# touch.net
KiCad netlist of a schematic drawn in Altium Designer
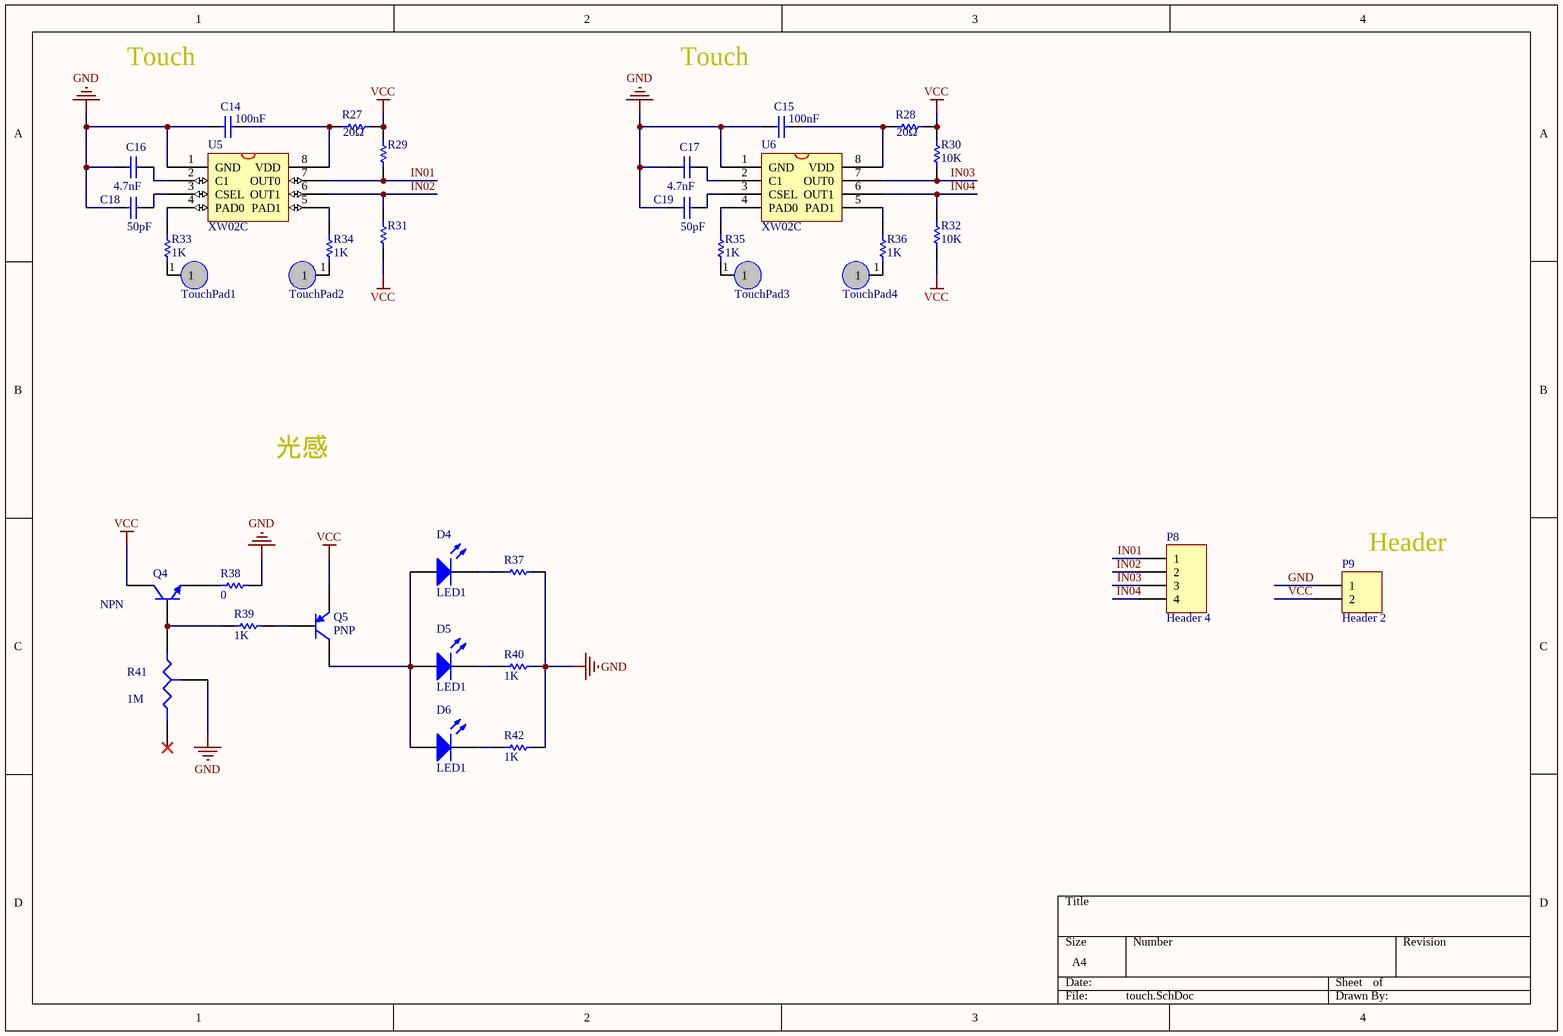
[diagram p0: touch.SchDoc]

(export (version "E")
  (design (tool "Eeschema 10.0.6"))
  (components
    (comp (ref "C14")
      (value "100nF")
      (footprint "0603p")
      (description "Capacitor")
      (fields (field (name "PUBLISHER") "Altium Limited"))
      (libsource (lib "Miscellaneous Devices") (part "Cap"))
    )
    (comp (ref "C15")
      (value "100nF")
      (footprint "0603p")
      (description "Capacitor")
      (fields (field (name "PUBLISHER") "Altium Limited"))
      (libsource (lib "Miscellaneous Devices") (part "Cap"))
    )
    (comp (ref "C16")
      (value "4.7nF")
      (footprint "0603p")
      (description "Capacitor")
      (fields (field (name "Comment") "4.7nf") (field (name "PUBLISHER") "Altium Limited"))
      (libsource (lib "Miscellaneous Devices") (part "Cap"))
    )
    (comp (ref "C17")
      (value "4.7nF")
      (footprint "0603p")
      (description "Capacitor")
      (fields (field (name "Comment") "4.7nf") (field (name "PUBLISHER") "Altium Limited"))
      (libsource (lib "Miscellaneous Devices") (part "Cap"))
    )
    (comp (ref "C18")
      (value "50pF")
      (footprint "0603p")
      (description "Capacitor")
      (fields (field (name "Comment") "50pf") (field (name "PUBLISHER") "Altium Limited"))
      (libsource (lib "Miscellaneous Devices") (part "Cap"))
    )
    (comp (ref "C19")
      (value "50pF")
      (footprint "0603p")
      (description "Capacitor")
      (fields (field (name "Comment") "50pf") (field (name "PUBLISHER") "Altium Limited"))
      (libsource (lib "Miscellaneous Devices") (part "Cap"))
    )
    (comp (ref "D4")
      (value "LED1")
      (footprint "0805")
      (description "Typical RED GaAs LED")
      (fields (field (name "PUBLISHER") "Altium Limited"))
      (libsource (lib "Miscellaneous Devices") (part "LED1"))
    )
    (comp (ref "D5")
      (value "LED1")
      (footprint "0805")
      (description "Typical RED GaAs LED")
      (fields (field (name "PUBLISHER") "Altium Limited"))
      (libsource (lib "Miscellaneous Devices") (part "LED1"))
    )
    (comp (ref "D6")
      (value "LED1")
      (footprint "0805")
      (description "Typical RED GaAs LED")
      (fields (field (name "PUBLISHER") "Altium Limited"))
      (libsource (lib "Miscellaneous Devices") (part "LED1"))
    )
    (comp (ref "P8")
      (value "Header 4")
      (footprint "HDR1X4")
      (description "Header, 4-Pin")
      (fields (field (name "PUBLISHER") "Altium Limited"))
      (libsource (lib "Miscellaneous Connectors") (part "Header 4"))
    )
    (comp (ref "P9")
      (value "Header 2")
      (footprint "HDR1X2")
      (description "Header, 2-Pin")
      (fields (field (name "PUBLISHER") "Altium Limited"))
      (libsource (lib "Miscellaneous Connectors") (part "Header 2"))
    )
    (comp (ref "Q4")
      (value "NPN")
      (footprint "TEMT6000X01")
      (description "NPN Bipolar Transistor")
      (fields (field (name "PUBLISHER") "Altium Limited"))
      (libsource (lib "Miscellaneous Devices") (part "NPN"))
    )
    (comp (ref "Q5")
      (value "PNP")
      (footprint "SOT-23R")
      (description "8550")
      (fields (field (name "PUBLISHER") "Altium Limited"))
      (libsource (lib "Miscellaneous Devices") (part "PNP"))
    )
    (comp (ref "R27")
      (value "20Ω")
      (footprint "0603p")
      (description "Resistor")
      (fields (field (name "PUBLISHER") "Altium Limited"))
      (libsource (lib "Miscellaneous Devices") (part "Res1"))
    )
    (comp (ref "R28")
      (value "20Ω")
      (footprint "0603p")
      (description "Resistor")
      (fields (field (name "PUBLISHER") "Altium Limited"))
      (libsource (lib "Miscellaneous Devices") (part "Res1"))
    )
    (comp (ref "R29")
      (value "10K")
      (footprint "0603p")
      (description "Resistor")
      (fields (field (name "PUBLISHER") "Altium Limited"))
      (libsource (lib "Miscellaneous Devices") (part "Res1"))
    )
    (comp (ref "R30")
      (value "10K")
      (footprint "0603p")
      (description "Resistor")
      (fields (field (name "PUBLISHER") "Altium Limited"))
      (libsource (lib "Miscellaneous Devices") (part "Res1"))
    )
    (comp (ref "R31")
      (value "10K")
      (footprint "0603p")
      (description "Resistor")
      (fields (field (name "PUBLISHER") "Altium Limited"))
      (libsource (lib "Miscellaneous Devices") (part "Res1"))
    )
    (comp (ref "R32")
      (value "10K")
      (footprint "0603p")
      (description "Resistor")
      (fields (field (name "PUBLISHER") "Altium Limited"))
      (libsource (lib "Miscellaneous Devices") (part "Res1"))
    )
    (comp (ref "R33")
      (value "1K")
      (footprint "0603p")
      (description "Resistor")
      (fields (field (name "PUBLISHER") "Altium Limited"))
      (libsource (lib "Miscellaneous Devices") (part "Res1"))
    )
    (comp (ref "R34")
      (value "1K")
      (footprint "0603p")
      (description "Resistor")
      (fields (field (name "PUBLISHER") "Altium Limited"))
      (libsource (lib "Miscellaneous Devices") (part "Res1"))
    )
    (comp (ref "R35")
      (value "1K")
      (footprint "0603p")
      (description "Resistor")
      (fields (field (name "PUBLISHER") "Altium Limited"))
      (libsource (lib "Miscellaneous Devices") (part "Res1"))
    )
    (comp (ref "R36")
      (value "1K")
      (footprint "0603p")
      (description "Resistor")
      (fields (field (name "PUBLISHER") "Altium Limited"))
      (libsource (lib "Miscellaneous Devices") (part "Res1"))
    )
    (comp (ref "R37")
      (value "1K")
      (footprint "0603p")
      (description "Resistor")
      (fields (field (name "PUBLISHER") "Altium Limited"))
      (libsource (lib "Miscellaneous Devices") (part "Res1"))
    )
    (comp (ref "R38")
      (value "0")
      (footprint "0603p")
      (description "Resistor")
      (fields (field (name "PUBLISHER") "Altium Limited"))
      (libsource (lib "Miscellaneous Devices") (part "Res1"))
    )
    (comp (ref "R39")
      (value "1K")
      (footprint "0603p")
      (description "Resistor")
      (libsource (lib "Miscellaneous Devices") (part "Res1"))
    )
    (comp (ref "R40")
      (value "1K")
      (footprint "0603p")
      (description "Resistor")
      (fields (field (name "PUBLISHER") "Altium Limited"))
      (libsource (lib "Miscellaneous Devices") (part "Res1"))
    )
    (comp (ref "R41")
      (value "1M")
      (footprint "RM063")
      (description "Tapped Resistor")
      (libsource (lib "Miscellaneous Devices") (part "Res Tap"))
    )
    (comp (ref "R42")
      (value "1K")
      (footprint "0603p")
      (description "Resistor")
      (fields (field (name "PUBLISHER") "Altium Limited"))
      (libsource (lib "Miscellaneous Devices") (part "Res1"))
    )
    (comp (ref "TouchPad1")
      (value "TouchPad")
      (footprint "TOUCHKEY - latch")
      (libsource (lib "PCB_Project1") (part "TouchPad"))
    )
    (comp (ref "TouchPad2")
      (value "TouchPad")
      (footprint "TOUCHKEY - latch")
      (libsource (lib "PCB_Project1") (part "TouchPad"))
    )
    (comp (ref "TouchPad3")
      (value "TouchPad")
      (footprint "TOUCHKEY - latch")
      (libsource (lib "PCB_Project1") (part "TouchPad"))
    )
    (comp (ref "TouchPad4")
      (value "TouchPad")
      (footprint "TOUCHKEY - latch")
      (libsource (lib "PCB_Project1") (part "TouchPad"))
    )
    (comp (ref "U5") (value "XW02C") (footprint "SOP-8L") (libsource (lib "EliteSTM32封装库") (part "24C256")))
    (comp (ref "U6") (value "XW02C") (footprint "SOP-8L") (libsource (lib "EliteSTM32封装库") (part "24C256")))
  )
  (nets
    (net (code "2") (name "/IN01") (class "Default")
      (node (ref "P8") (pin "1") (pinfunction "1_1") (pintype "passive"))
      (node (ref "R29") (pin "1") (pinfunction "1_1") (pintype "passive"))
      (node (ref "U5") (pin "7") (pinfunction "OUT0_7") (pintype "bidirectional"))
    )
    (net (code "3") (name "/IN02") (class "Default")
      (node (ref "P8") (pin "2") (pinfunction "2_2") (pintype "passive"))
      (node (ref "R31") (pin "2") (pinfunction "2_2") (pintype "passive"))
      (node (ref "U5") (pin "6") (pinfunction "OUT1_6") (pintype "bidirectional"))
    )
    (net (code "4") (name "/IN03") (class "Default")
      (node (ref "P8") (pin "3") (pinfunction "3_3") (pintype "passive"))
      (node (ref "R30") (pin "1") (pinfunction "1_1") (pintype "passive"))
      (node (ref "U6") (pin "7") (pinfunction "OUT0_7") (pintype "bidirectional"))
    )
    (net (code "5") (name "/IN04") (class "Default")
      (node (ref "P8") (pin "4") (pinfunction "4_4") (pintype "passive"))
      (node (ref "R32") (pin "2") (pinfunction "2_2") (pintype "passive"))
      (node (ref "U6") (pin "6") (pinfunction "OUT1_6") (pintype "bidirectional"))
    )
    (net (code "6") (name "GND") (class "Default")
      (node (ref "C14") (pin "1") (pinfunction "1_1") (pintype "passive"))
      (node (ref "C15") (pin "1") (pinfunction "1_1") (pintype "passive"))
      (node (ref "C16") (pin "1") (pinfunction "1_1") (pintype "passive"))
      (node (ref "C17") (pin "1") (pinfunction "1_1") (pintype "passive"))
      (node (ref "C18") (pin "1") (pinfunction "1_1") (pintype "passive"))
      (node (ref "C19") (pin "1") (pinfunction "1_1") (pintype "passive"))
      (node (ref "P9") (pin "1") (pinfunction "1_1") (pintype "passive"))
      (node (ref "R37") (pin "1") (pinfunction "1_1") (pintype "passive"))
      (node (ref "R38") (pin "1") (pinfunction "1_1") (pintype "passive"))
      (node (ref "R40") (pin "1") (pinfunction "1_1") (pintype "passive"))
      (node (ref "R41") (pin "2") (pinfunction "TAP_2") (pintype "passive"))
      (node (ref "R42") (pin "1") (pinfunction "1_1") (pintype "passive"))
      (node (ref "U5") (pin "1") (pinfunction "GND_1") (pintype "power_in"))
      (node (ref "U6") (pin "1") (pinfunction "GND_1") (pintype "power_in"))
    )
    (net (code "7") (name "Net-(D4-A)") (class "Default")
      (node (ref "D4") (pin "1") (pinfunction "A_1") (pintype "passive"))
      (node (ref "D5") (pin "1") (pinfunction "A_1") (pintype "passive"))
      (node (ref "D6") (pin "1") (pinfunction "A_1") (pintype "passive"))
      (node (ref "Q5") (pin "1") (pinfunction "C_1") (pintype "passive"))
    )
    (net (code "8") (name "Net-(D4-K)") (class "Default")
      (node (ref "D4") (pin "2") (pinfunction "K_2") (pintype "passive"))
      (node (ref "R37") (pin "2") (pinfunction "2_2") (pintype "passive"))
    )
    (net (code "9") (name "Net-(D5-K)") (class "Default")
      (node (ref "D5") (pin "2") (pinfunction "K_2") (pintype "passive"))
      (node (ref "R40") (pin "2") (pinfunction "2_2") (pintype "passive"))
    )
    (net (code "10") (name "Net-(D6-K)") (class "Default")
      (node (ref "D6") (pin "2") (pinfunction "K_2") (pintype "passive"))
      (node (ref "R42") (pin "2") (pinfunction "2_2") (pintype "passive"))
    )
    (net (code "11") (name "Net-(Q4-B)") (class "Default")
      (node (ref "Q4") (pin "2") (pinfunction "B_2") (pintype "passive"))
      (node (ref "R39") (pin "2") (pinfunction "2_2") (pintype "passive"))
      (node (ref "R41") (pin "1") (pinfunction "A_1") (pintype "passive"))
    )
    (net (code "12") (name "Net-(Q4-E)") (class "Default")
      (node (ref "Q4") (pin "3") (pinfunction "E_3") (pintype "passive"))
      (node (ref "R38") (pin "2") (pinfunction "2_2") (pintype "passive"))
    )
    (net (code "13") (name "Net-(Q5-B)") (class "Default")
      (node (ref "Q5") (pin "2") (pinfunction "B_2") (pintype "passive"))
      (node (ref "R39") (pin "1") (pinfunction "1_1") (pintype "passive"))
    )
    (net (code "14") (name "Net-(R33-Pad1)") (class "Default")
      (node (ref "R33") (pin "1") (pinfunction "1_1") (pintype "passive"))
      (node (ref "TouchPad1") (pin "1") (pinfunction "1_1") (pintype "passive"))
    )
    (net (code "15") (name "Net-(R34-Pad1)") (class "Default")
      (node (ref "R34") (pin "1") (pinfunction "1_1") (pintype "passive"))
      (node (ref "TouchPad2") (pin "1") (pinfunction "1_1") (pintype "passive"))
    )
    (net (code "16") (name "Net-(R35-Pad1)") (class "Default")
      (node (ref "R35") (pin "1") (pinfunction "1_1") (pintype "passive"))
      (node (ref "TouchPad3") (pin "1") (pinfunction "1_1") (pintype "passive"))
    )
    (net (code "17") (name "Net-(R36-Pad1)") (class "Default")
      (node (ref "R36") (pin "1") (pinfunction "1_1") (pintype "passive"))
      (node (ref "TouchPad4") (pin "1") (pinfunction "1_1") (pintype "passive"))
    )
    (net (code "18") (name "Net-(U5-C1)") (class "Default")
      (node (ref "C16") (pin "2") (pinfunction "2_2") (pintype "passive"))
      (node (ref "U5") (pin "2") (pinfunction "C1_2") (pintype "bidirectional"))
    )
    (net (code "19") (name "Net-(U5-CSEL)") (class "Default")
      (node (ref "C18") (pin "2") (pinfunction "2_2") (pintype "passive"))
      (node (ref "U5") (pin "3") (pinfunction "CSEL_3") (pintype "bidirectional"))
    )
    (net (code "20") (name "Net-(U5-PAD0)") (class "Default")
      (node (ref "R33") (pin "2") (pinfunction "2_2") (pintype "passive"))
      (node (ref "U5") (pin "4") (pinfunction "PAD0_4") (pintype "bidirectional"))
    )
    (net (code "21") (name "Net-(U5-PAD1)") (class "Default")
      (node (ref "R34") (pin "2") (pinfunction "2_2") (pintype "passive"))
      (node (ref "U5") (pin "5") (pinfunction "PAD1_5") (pintype "bidirectional"))
    )
    (net (code "22") (name "Net-(U5-VDD)") (class "Default")
      (node (ref "C14") (pin "2") (pinfunction "2_2") (pintype "passive"))
      (node (ref "R27") (pin "1") (pinfunction "1_1") (pintype "passive"))
      (node (ref "U5") (pin "8") (pinfunction "VDD_8") (pintype "power_in"))
    )
    (net (code "23") (name "Net-(U6-C1)") (class "Default")
      (node (ref "C17") (pin "2") (pinfunction "2_2") (pintype "passive"))
      (node (ref "U6") (pin "2") (pinfunction "C1_2") (pintype "bidirectional"))
    )
    (net (code "24") (name "Net-(U6-CSEL)") (class "Default")
      (node (ref "C19") (pin "2") (pinfunction "2_2") (pintype "passive"))
      (node (ref "U6") (pin "3") (pinfunction "CSEL_3") (pintype "bidirectional"))
    )
    (net (code "25") (name "Net-(U6-PAD0)") (class "Default")
      (node (ref "R35") (pin "2") (pinfunction "2_2") (pintype "passive"))
      (node (ref "U6") (pin "4") (pinfunction "PAD0_4") (pintype "bidirectional"))
    )
    (net (code "26") (name "Net-(U6-PAD1)") (class "Default")
      (node (ref "R36") (pin "2") (pinfunction "2_2") (pintype "passive"))
      (node (ref "U6") (pin "5") (pinfunction "PAD1_5") (pintype "bidirectional"))
    )
    (net (code "27") (name "Net-(U6-VDD)") (class "Default")
      (node (ref "C15") (pin "2") (pinfunction "2_2") (pintype "passive"))
      (node (ref "R28") (pin "1") (pinfunction "1_1") (pintype "passive"))
      (node (ref "U6") (pin "8") (pinfunction "VDD_8") (pintype "power_in"))
    )
    (net (code "28") (name "VCC") (class "Default")
      (node (ref "P9") (pin "2") (pinfunction "2_2") (pintype "passive"))
      (node (ref "Q4") (pin "1") (pinfunction "C_1") (pintype "passive"))
      (node (ref "Q5") (pin "3") (pinfunction "E_3") (pintype "passive"))
      (node (ref "R27") (pin "2") (pinfunction "2_2") (pintype "passive"))
      (node (ref "R28") (pin "2") (pinfunction "2_2") (pintype "passive"))
      (node (ref "R29") (pin "2") (pinfunction "2_2") (pintype "passive"))
      (node (ref "R30") (pin "2") (pinfunction "2_2") (pintype "passive"))
      (node (ref "R31") (pin "1") (pinfunction "1_1") (pintype "passive"))
      (node (ref "R32") (pin "1") (pinfunction "1_1") (pintype "passive"))
    )
    (net (code "29") (name "unconnected-(R41-B-Pad3)") (class "Default")
      (node (ref "R41") (pin "3") (pinfunction "B_3") (pintype "passive+no_connect"))
    )
  )
)
